# Pressure_SENSOR.net
KiCad netlist of a schematic drawn in Altium Designer
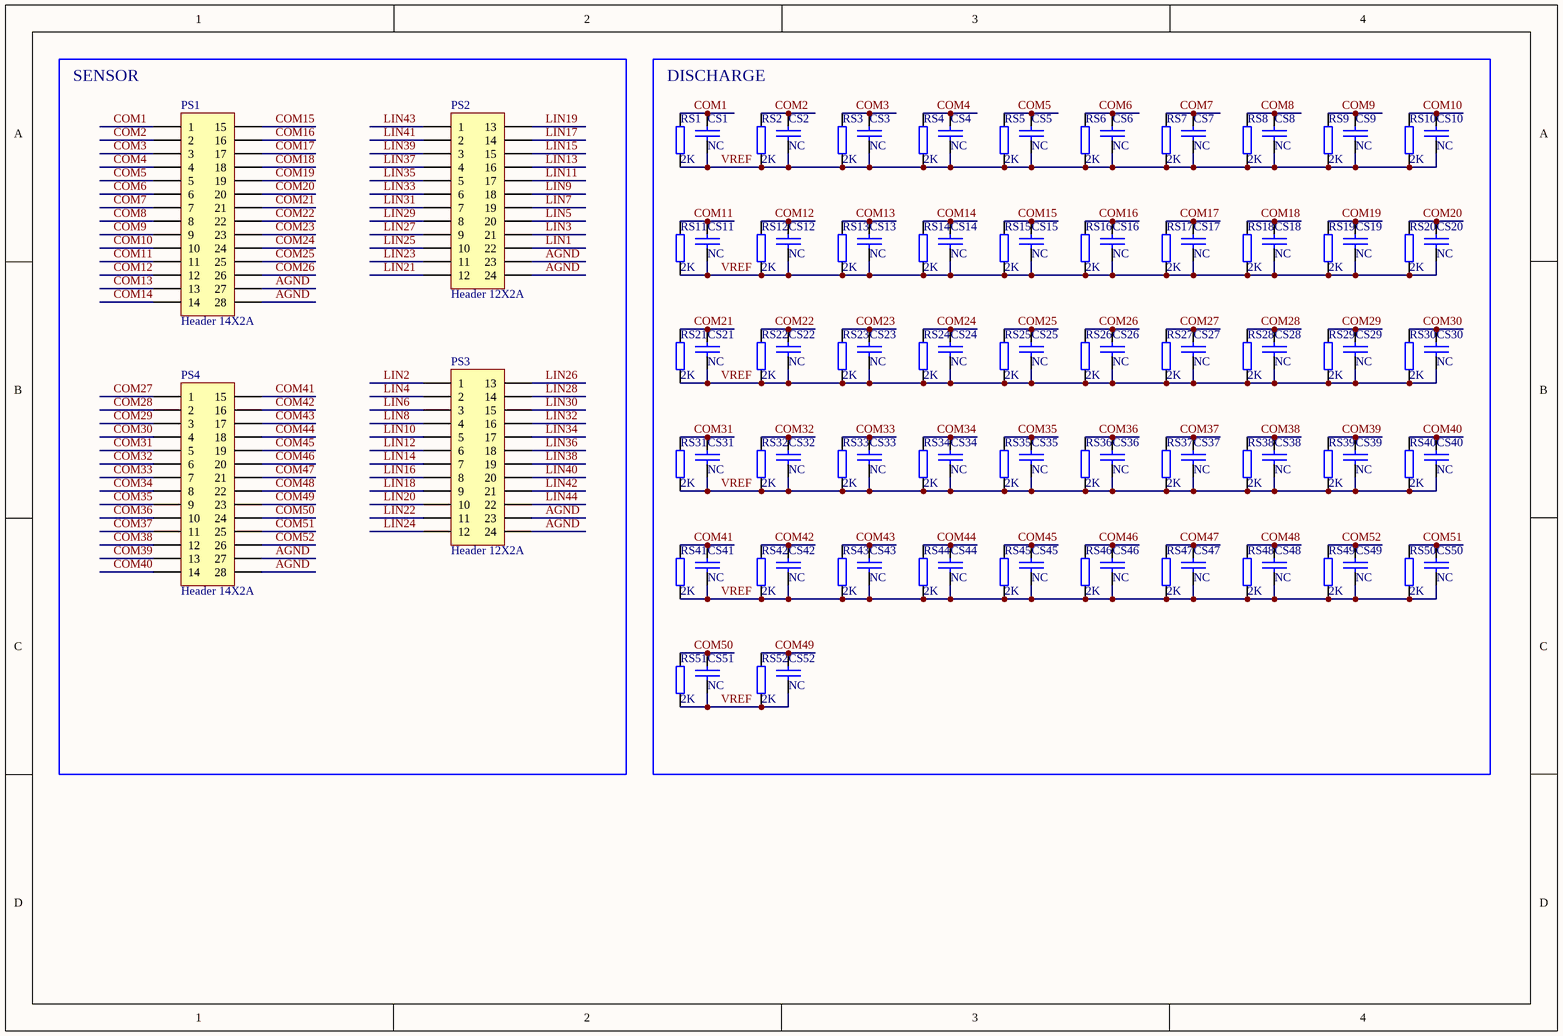
[diagram p0: Pressure_SENSOR.SchDoc]

(export (version "E")
  (design (tool "Eeschema 10.0.6"))
  (components
    (comp (ref "CS1")
      (value "NC")
      (footprint "c0603_HSC100")
      (description "Capacitor")
      (libsource (lib "*") (part "CAP"))
    )
    (comp (ref "CS2")
      (value "NC")
      (footprint "c0603_HSC100")
      (description "Capacitor")
      (libsource (lib "*") (part "CAP"))
    )
    (comp (ref "CS3")
      (value "NC")
      (footprint "c0603_HSC100")
      (description "Capacitor")
      (libsource (lib "*") (part "CAP"))
    )
    (comp (ref "CS4")
      (value "NC")
      (footprint "c0603_HSC100")
      (description "Capacitor")
      (libsource (lib "*") (part "CAP"))
    )
    (comp (ref "CS5")
      (value "NC")
      (footprint "c0603_HSC100")
      (description "Capacitor")
      (libsource (lib "*") (part "CAP"))
    )
    (comp (ref "CS6")
      (value "NC")
      (footprint "c0603_HSC100")
      (description "Capacitor")
      (libsource (lib "*") (part "CAP"))
    )
    (comp (ref "CS7")
      (value "NC")
      (footprint "c0603_HSC100")
      (description "Capacitor")
      (libsource (lib "*") (part "CAP"))
    )
    (comp (ref "CS8")
      (value "NC")
      (footprint "c0603_HSC100")
      (description "Capacitor")
      (libsource (lib "*") (part "CAP"))
    )
    (comp (ref "CS9")
      (value "NC")
      (footprint "c0603_HSC100")
      (description "Capacitor")
      (libsource (lib "*") (part "CAP"))
    )
    (comp (ref "CS10")
      (value "NC")
      (footprint "c0603_HSC100")
      (description "Capacitor")
      (libsource (lib "*") (part "CAP"))
    )
    (comp (ref "CS11")
      (value "NC")
      (footprint "c0603_HSC100")
      (description "Capacitor")
      (libsource (lib "*") (part "CAP"))
    )
    (comp (ref "CS12")
      (value "NC")
      (footprint "c0603_HSC100")
      (description "Capacitor")
      (libsource (lib "*") (part "CAP"))
    )
    (comp (ref "CS13")
      (value "NC")
      (footprint "c0603_HSC100")
      (description "Capacitor")
      (libsource (lib "*") (part "CAP"))
    )
    (comp (ref "CS14")
      (value "NC")
      (footprint "c0603_HSC100")
      (description "Capacitor")
      (libsource (lib "*") (part "CAP"))
    )
    (comp (ref "CS15")
      (value "NC")
      (footprint "c0603_HSC100")
      (description "Capacitor")
      (libsource (lib "*") (part "CAP"))
    )
    (comp (ref "CS16")
      (value "NC")
      (footprint "c0603_HSC100")
      (description "Capacitor")
      (libsource (lib "*") (part "CAP"))
    )
    (comp (ref "CS17")
      (value "NC")
      (footprint "c0603_HSC100")
      (description "Capacitor")
      (libsource (lib "*") (part "CAP"))
    )
    (comp (ref "CS18")
      (value "NC")
      (footprint "c0603_HSC100")
      (description "Capacitor")
      (libsource (lib "*") (part "CAP"))
    )
    (comp (ref "CS19")
      (value "NC")
      (footprint "c0603_HSC100")
      (description "Capacitor")
      (libsource (lib "*") (part "CAP"))
    )
    (comp (ref "CS20")
      (value "NC")
      (footprint "c0603_HSC100")
      (description "Capacitor")
      (libsource (lib "*") (part "CAP"))
    )
    (comp (ref "CS21")
      (value "NC")
      (footprint "c0603_HSC100")
      (description "Capacitor")
      (libsource (lib "*") (part "CAP"))
    )
    (comp (ref "CS22")
      (value "NC")
      (footprint "c0603_HSC100")
      (description "Capacitor")
      (libsource (lib "*") (part "CAP"))
    )
    (comp (ref "CS23")
      (value "NC")
      (footprint "c0603_HSC100")
      (description "Capacitor")
      (libsource (lib "*") (part "CAP"))
    )
    (comp (ref "CS24")
      (value "NC")
      (footprint "c0603_HSC100")
      (description "Capacitor")
      (libsource (lib "*") (part "CAP"))
    )
    (comp (ref "CS25")
      (value "NC")
      (footprint "c0603_HSC100")
      (description "Capacitor")
      (libsource (lib "*") (part "CAP"))
    )
    (comp (ref "CS26")
      (value "NC")
      (footprint "c0603_HSC100")
      (description "Capacitor")
      (libsource (lib "*") (part "CAP"))
    )
    (comp (ref "CS27")
      (value "NC")
      (footprint "c0603_HSC100")
      (description "Capacitor")
      (libsource (lib "*") (part "CAP"))
    )
    (comp (ref "CS28")
      (value "NC")
      (footprint "c0603_HSC100")
      (description "Capacitor")
      (libsource (lib "*") (part "CAP"))
    )
    (comp (ref "CS29")
      (value "NC")
      (footprint "c0603_HSC100")
      (description "Capacitor")
      (libsource (lib "*") (part "CAP"))
    )
    (comp (ref "CS30")
      (value "NC")
      (footprint "c0603_HSC100")
      (description "Capacitor")
      (libsource (lib "*") (part "CAP"))
    )
    (comp (ref "CS31")
      (value "NC")
      (footprint "c0603_HSC100")
      (description "Capacitor")
      (libsource (lib "*") (part "CAP"))
    )
    (comp (ref "CS32")
      (value "NC")
      (footprint "c0603_HSC100")
      (description "Capacitor")
      (libsource (lib "*") (part "CAP"))
    )
    (comp (ref "CS33")
      (value "NC")
      (footprint "c0603_HSC100")
      (description "Capacitor")
      (libsource (lib "*") (part "CAP"))
    )
    (comp (ref "CS34")
      (value "NC")
      (footprint "c0603_HSC100")
      (description "Capacitor")
      (libsource (lib "*") (part "CAP"))
    )
    (comp (ref "CS35")
      (value "NC")
      (footprint "c0603_HSC100")
      (description "Capacitor")
      (libsource (lib "*") (part "CAP"))
    )
    (comp (ref "CS36")
      (value "NC")
      (footprint "c0603_HSC100")
      (description "Capacitor")
      (libsource (lib "*") (part "CAP"))
    )
    (comp (ref "CS37")
      (value "NC")
      (footprint "c0603_HSC100")
      (description "Capacitor")
      (libsource (lib "*") (part "CAP"))
    )
    (comp (ref "CS38")
      (value "NC")
      (footprint "c0603_HSC100")
      (description "Capacitor")
      (libsource (lib "*") (part "CAP"))
    )
    (comp (ref "CS39")
      (value "NC")
      (footprint "c0603_HSC100")
      (description "Capacitor")
      (libsource (lib "*") (part "CAP"))
    )
    (comp (ref "CS40")
      (value "NC")
      (footprint "c0603_HSC100")
      (description "Capacitor")
      (libsource (lib "*") (part "CAP"))
    )
    (comp (ref "CS41")
      (value "NC")
      (footprint "c0603_HSC100")
      (description "Capacitor")
      (libsource (lib "*") (part "CAP"))
    )
    (comp (ref "CS42")
      (value "NC")
      (footprint "c0603_HSC100")
      (description "Capacitor")
      (libsource (lib "*") (part "CAP"))
    )
    (comp (ref "CS43")
      (value "NC")
      (footprint "c0603_HSC100")
      (description "Capacitor")
      (libsource (lib "*") (part "CAP"))
    )
    (comp (ref "CS44")
      (value "NC")
      (footprint "c0603_HSC100")
      (description "Capacitor")
      (libsource (lib "*") (part "CAP"))
    )
    (comp (ref "CS45")
      (value "NC")
      (footprint "c0603_HSC100")
      (description "Capacitor")
      (libsource (lib "*") (part "CAP"))
    )
    (comp (ref "CS46")
      (value "NC")
      (footprint "c0603_HSC100")
      (description "Capacitor")
      (libsource (lib "*") (part "CAP"))
    )
    (comp (ref "CS47")
      (value "NC")
      (footprint "c0603_HSC100")
      (description "Capacitor")
      (libsource (lib "*") (part "CAP"))
    )
    (comp (ref "CS48")
      (value "NC")
      (footprint "c0603_HSC100")
      (description "Capacitor")
      (libsource (lib "*") (part "CAP"))
    )
    (comp (ref "CS49")
      (value "NC")
      (footprint "c0603_HSC100")
      (description "Capacitor")
      (libsource (lib "*") (part "CAP"))
    )
    (comp (ref "CS50")
      (value "NC")
      (footprint "c0603_HSC100")
      (description "Capacitor")
      (libsource (lib "*") (part "CAP"))
    )
    (comp (ref "CS51")
      (value "NC")
      (footprint "c0603_HSC100")
      (description "Capacitor")
      (libsource (lib "*") (part "CAP"))
    )
    (comp (ref "CS52")
      (value "NC")
      (footprint "c0603_HSC100")
      (description "Capacitor")
      (libsource (lib "*") (part "CAP"))
    )
    (comp (ref "PS1")
      (value "Header 14X2A")
      (footprint "FPC-1.0-26")
      (description "Header, 14-Pin, Dual row")
      (fields (field (name "PUBLISHER") "Altium Limited"))
      (libsource (lib "Miscellaneous Connectors") (part "Header 14X2A"))
    )
    (comp (ref "PS2")
      (value "Header 12X2A")
      (footprint "FPC-1.0-22")
      (description "Header, 12-Pin, Dual row")
      (fields (field (name "PUBLISHER") "Altium Limited"))
      (libsource (lib "Miscellaneous Connectors") (part "Header 12X2A"))
    )
    (comp (ref "PS3")
      (value "Header 12X2A")
      (footprint "FPC-1.0-22")
      (description "Header, 12-Pin, Dual row")
      (fields (field (name "PUBLISHER") "Altium Limited"))
      (libsource (lib "Miscellaneous Connectors") (part "Header 12X2A"))
    )
    (comp (ref "PS4")
      (value "Header 14X2A")
      (footprint "FPC-1.0-26")
      (description "Header, 14-Pin, Dual row")
      (fields (field (name "PUBLISHER") "Altium Limited"))
      (libsource (lib "Miscellaneous Connectors") (part "Header 14X2A"))
    )
    (comp (ref "RS1") (value "2K") (footprint "R0603_HSC100") (libsource (lib "MY_SCH") (part "RES")))
    (comp (ref "RS2") (value "2K") (footprint "R0603_HSC100") (libsource (lib "MY_SCH") (part "RES")))
    (comp (ref "RS3") (value "2K") (footprint "R0603_HSC100") (libsource (lib "MY_SCH") (part "RES")))
    (comp (ref "RS4") (value "2K") (footprint "R0603_HSC100") (libsource (lib "MY_SCH") (part "RES")))
    (comp (ref "RS5") (value "2K") (footprint "R0603_HSC100") (libsource (lib "MY_SCH") (part "RES")))
    (comp (ref "RS6") (value "2K") (footprint "R0603_HSC100") (libsource (lib "MY_SCH") (part "RES")))
    (comp (ref "RS7") (value "2K") (footprint "R0603_HSC100") (libsource (lib "MY_SCH") (part "RES")))
    (comp (ref "RS8") (value "2K") (footprint "R0603_HSC100") (libsource (lib "MY_SCH") (part "RES")))
    (comp (ref "RS9") (value "2K") (footprint "R0603_HSC100") (libsource (lib "MY_SCH") (part "RES")))
    (comp (ref "RS10") (value "2K") (footprint "R0603_HSC100") (libsource (lib "MY_SCH") (part "RES")))
    (comp (ref "RS11") (value "2K") (footprint "R0603_HSC100") (libsource (lib "MY_SCH") (part "RES")))
    (comp (ref "RS12") (value "2K") (footprint "R0603_HSC100") (libsource (lib "MY_SCH") (part "RES")))
    (comp (ref "RS13") (value "2K") (footprint "R0603_HSC100") (libsource (lib "MY_SCH") (part "RES")))
    (comp (ref "RS14") (value "2K") (footprint "R0603_HSC100") (libsource (lib "MY_SCH") (part "RES")))
    (comp (ref "RS15") (value "2K") (footprint "R0603_HSC100") (libsource (lib "MY_SCH") (part "RES")))
    (comp (ref "RS16") (value "2K") (footprint "R0603_HSC100") (libsource (lib "MY_SCH") (part "RES")))
    (comp (ref "RS17") (value "2K") (footprint "R0603_HSC100") (libsource (lib "MY_SCH") (part "RES")))
    (comp (ref "RS18") (value "2K") (footprint "R0603_HSC100") (libsource (lib "MY_SCH") (part "RES")))
    (comp (ref "RS19") (value "2K") (footprint "R0603_HSC100") (libsource (lib "MY_SCH") (part "RES")))
    (comp (ref "RS20") (value "2K") (footprint "R0603_HSC100") (libsource (lib "MY_SCH") (part "RES")))
    (comp (ref "RS21") (value "2K") (footprint "R0603_HSC100") (libsource (lib "MY_SCH") (part "RES")))
    (comp (ref "RS22") (value "2K") (footprint "R0603_HSC100") (libsource (lib "MY_SCH") (part "RES")))
    (comp (ref "RS23") (value "2K") (footprint "R0603_HSC100") (libsource (lib "MY_SCH") (part "RES")))
    (comp (ref "RS24") (value "2K") (footprint "R0603_HSC100") (libsource (lib "MY_SCH") (part "RES")))
    (comp (ref "RS25") (value "2K") (footprint "R0603_HSC100") (libsource (lib "MY_SCH") (part "RES")))
    (comp (ref "RS26") (value "2K") (footprint "R0603_HSC100") (libsource (lib "MY_SCH") (part "RES")))
    (comp (ref "RS27") (value "2K") (footprint "R0603_HSC100") (libsource (lib "MY_SCH") (part "RES")))
    (comp (ref "RS28") (value "2K") (footprint "R0603_HSC100") (libsource (lib "MY_SCH") (part "RES")))
    (comp (ref "RS29") (value "2K") (footprint "R0603_HSC100") (libsource (lib "MY_SCH") (part "RES")))
    (comp (ref "RS30") (value "2K") (footprint "R0603_HSC100") (libsource (lib "MY_SCH") (part "RES")))
    (comp (ref "RS31") (value "2K") (footprint "R0603_HSC100") (libsource (lib "MY_SCH") (part "RES")))
    (comp (ref "RS32") (value "2K") (footprint "R0603_HSC100") (libsource (lib "MY_SCH") (part "RES")))
    (comp (ref "RS33") (value "2K") (footprint "R0603_HSC100") (libsource (lib "MY_SCH") (part "RES")))
    (comp (ref "RS34") (value "2K") (footprint "R0603_HSC100") (libsource (lib "MY_SCH") (part "RES")))
    (comp (ref "RS35") (value "2K") (footprint "R0603_HSC100") (libsource (lib "MY_SCH") (part "RES")))
    (comp (ref "RS36") (value "2K") (footprint "R0603_HSC100") (libsource (lib "MY_SCH") (part "RES")))
    (comp (ref "RS37") (value "2K") (footprint "R0603_HSC100") (libsource (lib "MY_SCH") (part "RES")))
    (comp (ref "RS38") (value "2K") (footprint "R0603_HSC100") (libsource (lib "MY_SCH") (part "RES")))
    (comp (ref "RS39") (value "2K") (footprint "R0603_HSC100") (libsource (lib "MY_SCH") (part "RES")))
    (comp (ref "RS40") (value "2K") (footprint "R0603_HSC100") (libsource (lib "MY_SCH") (part "RES")))
    (comp (ref "RS41") (value "2K") (footprint "R0603_HSC100") (libsource (lib "MY_SCH") (part "RES")))
    (comp (ref "RS42") (value "2K") (footprint "R0603_HSC100") (libsource (lib "MY_SCH") (part "RES")))
    (comp (ref "RS43") (value "2K") (footprint "R0603_HSC100") (libsource (lib "MY_SCH") (part "RES")))
    (comp (ref "RS44") (value "2K") (footprint "R0603_HSC100") (libsource (lib "MY_SCH") (part "RES")))
    (comp (ref "RS45") (value "2K") (footprint "R0603_HSC100") (libsource (lib "MY_SCH") (part "RES")))
    (comp (ref "RS46") (value "2K") (footprint "R0603_HSC100") (libsource (lib "MY_SCH") (part "RES")))
    (comp (ref "RS47") (value "2K") (footprint "R0603_HSC100") (libsource (lib "MY_SCH") (part "RES")))
    (comp (ref "RS48") (value "2K") (footprint "R0603_HSC100") (libsource (lib "MY_SCH") (part "RES")))
    (comp (ref "RS49") (value "2K") (footprint "R0603_HSC100") (libsource (lib "MY_SCH") (part "RES")))
    (comp (ref "RS50") (value "2K") (footprint "R0603_HSC100") (libsource (lib "MY_SCH") (part "RES")))
    (comp (ref "RS51") (value "2K") (footprint "R0603_HSC100") (libsource (lib "MY_SCH") (part "RES")))
    (comp (ref "RS52") (value "2K") (footprint "R0603_HSC100") (libsource (lib "MY_SCH") (part "RES")))
  )
  (nets
    (net (code "1") (name "/AGND") (class "Default")
      (node (ref "PS1") (pin "27") (pinfunction "27_27") (pintype "passive"))
      (node (ref "PS1") (pin "28") (pinfunction "28_28") (pintype "passive"))
      (node (ref "PS2") (pin "23") (pinfunction "23_23") (pintype "passive"))
      (node (ref "PS2") (pin "24") (pinfunction "24_24") (pintype "passive"))
      (node (ref "PS3") (pin "23") (pinfunction "23_23") (pintype "passive"))
      (node (ref "PS3") (pin "24") (pinfunction "24_24") (pintype "passive"))
      (node (ref "PS4") (pin "27") (pinfunction "27_27") (pintype "passive"))
      (node (ref "PS4") (pin "28") (pinfunction "28_28") (pintype "passive"))
    )
    (net (code "2") (name "/COM1") (class "Default")
      (node (ref "CS1") (pin "2") (pinfunction "2_2") (pintype "passive"))
      (node (ref "PS1") (pin "1") (pinfunction "1_1") (pintype "passive"))
      (node (ref "RS1") (pin "2") (pintype "passive"))
    )
    (net (code "3") (name "/COM2") (class "Default")
      (node (ref "CS2") (pin "2") (pinfunction "2_2") (pintype "passive"))
      (node (ref "PS1") (pin "2") (pinfunction "2_2") (pintype "passive"))
      (node (ref "RS2") (pin "2") (pintype "passive"))
    )
    (net (code "4") (name "/COM3") (class "Default")
      (node (ref "CS3") (pin "2") (pinfunction "2_2") (pintype "passive"))
      (node (ref "PS1") (pin "3") (pinfunction "3_3") (pintype "passive"))
      (node (ref "RS3") (pin "2") (pintype "passive"))
    )
    (net (code "5") (name "/COM4") (class "Default")
      (node (ref "CS4") (pin "2") (pinfunction "2_2") (pintype "passive"))
      (node (ref "PS1") (pin "4") (pinfunction "4_4") (pintype "passive"))
      (node (ref "RS4") (pin "2") (pintype "passive"))
    )
    (net (code "6") (name "/COM5") (class "Default")
      (node (ref "CS5") (pin "2") (pinfunction "2_2") (pintype "passive"))
      (node (ref "PS1") (pin "5") (pinfunction "5_5") (pintype "passive"))
      (node (ref "RS5") (pin "2") (pintype "passive"))
    )
    (net (code "7") (name "/COM6") (class "Default")
      (node (ref "CS6") (pin "2") (pinfunction "2_2") (pintype "passive"))
      (node (ref "PS1") (pin "6") (pinfunction "6_6") (pintype "passive"))
      (node (ref "RS6") (pin "2") (pintype "passive"))
    )
    (net (code "8") (name "/COM7") (class "Default")
      (node (ref "CS7") (pin "2") (pinfunction "2_2") (pintype "passive"))
      (node (ref "PS1") (pin "7") (pinfunction "7_7") (pintype "passive"))
      (node (ref "RS7") (pin "2") (pintype "passive"))
    )
    (net (code "9") (name "/COM8") (class "Default")
      (node (ref "CS8") (pin "2") (pinfunction "2_2") (pintype "passive"))
      (node (ref "PS1") (pin "8") (pinfunction "8_8") (pintype "passive"))
      (node (ref "RS8") (pin "2") (pintype "passive"))
    )
    (net (code "10") (name "/COM9") (class "Default")
      (node (ref "CS9") (pin "2") (pinfunction "2_2") (pintype "passive"))
      (node (ref "PS1") (pin "9") (pinfunction "9_9") (pintype "passive"))
      (node (ref "RS9") (pin "2") (pintype "passive"))
    )
    (net (code "11") (name "/COM10") (class "Default")
      (node (ref "CS10") (pin "2") (pinfunction "2_2") (pintype "passive"))
      (node (ref "PS1") (pin "10") (pinfunction "10_10") (pintype "passive"))
      (node (ref "RS10") (pin "2") (pintype "passive"))
    )
    (net (code "12") (name "/COM11") (class "Default")
      (node (ref "CS11") (pin "2") (pinfunction "2_2") (pintype "passive"))
      (node (ref "PS1") (pin "11") (pinfunction "11_11") (pintype "passive"))
      (node (ref "RS11") (pin "2") (pintype "passive"))
    )
    (net (code "13") (name "/COM12") (class "Default")
      (node (ref "CS12") (pin "2") (pinfunction "2_2") (pintype "passive"))
      (node (ref "PS1") (pin "12") (pinfunction "12_12") (pintype "passive"))
      (node (ref "RS12") (pin "2") (pintype "passive"))
    )
    (net (code "14") (name "/COM13") (class "Default")
      (node (ref "CS13") (pin "2") (pinfunction "2_2") (pintype "passive"))
      (node (ref "PS1") (pin "13") (pinfunction "13_13") (pintype "passive"))
      (node (ref "RS13") (pin "2") (pintype "passive"))
    )
    (net (code "15") (name "/COM14") (class "Default")
      (node (ref "CS14") (pin "2") (pinfunction "2_2") (pintype "passive"))
      (node (ref "PS1") (pin "14") (pinfunction "14_14") (pintype "passive"))
      (node (ref "RS14") (pin "2") (pintype "passive"))
    )
    (net (code "16") (name "/COM15") (class "Default")
      (node (ref "CS15") (pin "2") (pinfunction "2_2") (pintype "passive"))
      (node (ref "PS1") (pin "15") (pinfunction "15_15") (pintype "passive"))
      (node (ref "RS15") (pin "2") (pintype "passive"))
    )
    (net (code "17") (name "/COM16") (class "Default")
      (node (ref "CS16") (pin "2") (pinfunction "2_2") (pintype "passive"))
      (node (ref "PS1") (pin "16") (pinfunction "16_16") (pintype "passive"))
      (node (ref "RS16") (pin "2") (pintype "passive"))
    )
    (net (code "18") (name "/COM17") (class "Default")
      (node (ref "CS17") (pin "2") (pinfunction "2_2") (pintype "passive"))
      (node (ref "PS1") (pin "17") (pinfunction "17_17") (pintype "passive"))
      (node (ref "RS17") (pin "2") (pintype "passive"))
    )
    (net (code "19") (name "/COM18") (class "Default")
      (node (ref "CS18") (pin "2") (pinfunction "2_2") (pintype "passive"))
      (node (ref "PS1") (pin "18") (pinfunction "18_18") (pintype "passive"))
      (node (ref "RS18") (pin "2") (pintype "passive"))
    )
    (net (code "20") (name "/COM19") (class "Default")
      (node (ref "CS19") (pin "2") (pinfunction "2_2") (pintype "passive"))
      (node (ref "PS1") (pin "19") (pinfunction "19_19") (pintype "passive"))
      (node (ref "RS19") (pin "2") (pintype "passive"))
    )
    (net (code "21") (name "/COM20") (class "Default")
      (node (ref "CS20") (pin "2") (pinfunction "2_2") (pintype "passive"))
      (node (ref "PS1") (pin "20") (pinfunction "20_20") (pintype "passive"))
      (node (ref "RS20") (pin "2") (pintype "passive"))
    )
    (net (code "22") (name "/COM21") (class "Default")
      (node (ref "CS21") (pin "2") (pinfunction "2_2") (pintype "passive"))
      (node (ref "PS1") (pin "21") (pinfunction "21_21") (pintype "passive"))
      (node (ref "RS21") (pin "2") (pintype "passive"))
    )
    (net (code "23") (name "/COM22") (class "Default")
      (node (ref "CS22") (pin "2") (pinfunction "2_2") (pintype "passive"))
      (node (ref "PS1") (pin "22") (pinfunction "22_22") (pintype "passive"))
      (node (ref "RS22") (pin "2") (pintype "passive"))
    )
    (net (code "24") (name "/COM23") (class "Default")
      (node (ref "CS23") (pin "2") (pinfunction "2_2") (pintype "passive"))
      (node (ref "PS1") (pin "23") (pinfunction "23_23") (pintype "passive"))
      (node (ref "RS23") (pin "2") (pintype "passive"))
    )
    (net (code "25") (name "/COM24") (class "Default")
      (node (ref "CS24") (pin "2") (pinfunction "2_2") (pintype "passive"))
      (node (ref "PS1") (pin "24") (pinfunction "24_24") (pintype "passive"))
      (node (ref "RS24") (pin "2") (pintype "passive"))
    )
    (net (code "26") (name "/COM25") (class "Default")
      (node (ref "CS25") (pin "2") (pinfunction "2_2") (pintype "passive"))
      (node (ref "PS1") (pin "25") (pinfunction "25_25") (pintype "passive"))
      (node (ref "RS25") (pin "2") (pintype "passive"))
    )
    (net (code "27") (name "/COM26") (class "Default")
      (node (ref "CS26") (pin "2") (pinfunction "2_2") (pintype "passive"))
      (node (ref "PS1") (pin "26") (pinfunction "26_26") (pintype "passive"))
      (node (ref "RS26") (pin "2") (pintype "passive"))
    )
    (net (code "28") (name "/COM27") (class "Default")
      (node (ref "CS27") (pin "2") (pinfunction "2_2") (pintype "passive"))
      (node (ref "PS4") (pin "1") (pinfunction "1_1") (pintype "passive"))
      (node (ref "RS27") (pin "2") (pintype "passive"))
    )
    (net (code "29") (name "/COM28") (class "Default")
      (node (ref "CS28") (pin "2") (pinfunction "2_2") (pintype "passive"))
      (node (ref "PS4") (pin "2") (pinfunction "2_2") (pintype "passive"))
      (node (ref "RS28") (pin "2") (pintype "passive"))
    )
    (net (code "30") (name "/COM29") (class "Default")
      (node (ref "CS29") (pin "2") (pinfunction "2_2") (pintype "passive"))
      (node (ref "PS4") (pin "3") (pinfunction "3_3") (pintype "passive"))
      (node (ref "RS29") (pin "2") (pintype "passive"))
    )
    (net (code "31") (name "/COM30") (class "Default")
      (node (ref "CS30") (pin "2") (pinfunction "2_2") (pintype "passive"))
      (node (ref "PS4") (pin "4") (pinfunction "4_4") (pintype "passive"))
      (node (ref "RS30") (pin "2") (pintype "passive"))
    )
    (net (code "32") (name "/COM31") (class "Default")
      (node (ref "CS31") (pin "2") (pinfunction "2_2") (pintype "passive"))
      (node (ref "PS4") (pin "5") (pinfunction "5_5") (pintype "passive"))
      (node (ref "RS31") (pin "2") (pintype "passive"))
    )
    (net (code "33") (name "/COM32") (class "Default")
      (node (ref "CS32") (pin "2") (pinfunction "2_2") (pintype "passive"))
      (node (ref "PS4") (pin "6") (pinfunction "6_6") (pintype "passive"))
      (node (ref "RS32") (pin "2") (pintype "passive"))
    )
    (net (code "34") (name "/COM33") (class "Default")
      (node (ref "CS33") (pin "2") (pinfunction "2_2") (pintype "passive"))
      (node (ref "PS4") (pin "7") (pinfunction "7_7") (pintype "passive"))
      (node (ref "RS33") (pin "2") (pintype "passive"))
    )
    (net (code "35") (name "/COM34") (class "Default")
      (node (ref "CS34") (pin "2") (pinfunction "2_2") (pintype "passive"))
      (node (ref "PS4") (pin "8") (pinfunction "8_8") (pintype "passive"))
      (node (ref "RS34") (pin "2") (pintype "passive"))
    )
    (net (code "36") (name "/COM35") (class "Default")
      (node (ref "CS35") (pin "2") (pinfunction "2_2") (pintype "passive"))
      (node (ref "PS4") (pin "9") (pinfunction "9_9") (pintype "passive"))
      (node (ref "RS35") (pin "2") (pintype "passive"))
    )
    (net (code "37") (name "/COM36") (class "Default")
      (node (ref "CS36") (pin "2") (pinfunction "2_2") (pintype "passive"))
      (node (ref "PS4") (pin "10") (pinfunction "10_10") (pintype "passive"))
      (node (ref "RS36") (pin "2") (pintype "passive"))
    )
    (net (code "38") (name "/COM37") (class "Default")
      (node (ref "CS37") (pin "2") (pinfunction "2_2") (pintype "passive"))
      (node (ref "PS4") (pin "11") (pinfunction "11_11") (pintype "passive"))
      (node (ref "RS37") (pin "2") (pintype "passive"))
    )
    (net (code "39") (name "/COM38") (class "Default")
      (node (ref "CS38") (pin "2") (pinfunction "2_2") (pintype "passive"))
      (node (ref "PS4") (pin "12") (pinfunction "12_12") (pintype "passive"))
      (node (ref "RS38") (pin "2") (pintype "passive"))
    )
    (net (code "40") (name "/COM39") (class "Default")
      (node (ref "CS39") (pin "2") (pinfunction "2_2") (pintype "passive"))
      (node (ref "PS4") (pin "13") (pinfunction "13_13") (pintype "passive"))
      (node (ref "RS39") (pin "2") (pintype "passive"))
    )
    (net (code "41") (name "/COM40") (class "Default")
      (node (ref "CS40") (pin "2") (pinfunction "2_2") (pintype "passive"))
      (node (ref "PS4") (pin "14") (pinfunction "14_14") (pintype "passive"))
      (node (ref "RS40") (pin "2") (pintype "passive"))
    )
    (net (code "42") (name "/COM41") (class "Default")
      (node (ref "CS41") (pin "2") (pinfunction "2_2") (pintype "passive"))
      (node (ref "PS4") (pin "15") (pinfunction "15_15") (pintype "passive"))
      (node (ref "RS41") (pin "2") (pintype "passive"))
    )
    (net (code "43") (name "/COM42") (class "Default")
      (node (ref "CS42") (pin "2") (pinfunction "2_2") (pintype "passive"))
      (node (ref "PS4") (pin "16") (pinfunction "16_16") (pintype "passive"))
      (node (ref "RS42") (pin "2") (pintype "passive"))
    )
    (net (code "44") (name "/COM43") (class "Default")
      (node (ref "CS43") (pin "2") (pinfunction "2_2") (pintype "passive"))
      (node (ref "PS4") (pin "17") (pinfunction "17_17") (pintype "passive"))
      (node (ref "RS43") (pin "2") (pintype "passive"))
    )
    (net (code "45") (name "/COM44") (class "Default")
      (node (ref "CS44") (pin "2") (pinfunction "2_2") (pintype "passive"))
      (node (ref "PS4") (pin "18") (pinfunction "18_18") (pintype "passive"))
      (node (ref "RS44") (pin "2") (pintype "passive"))
    )
    (net (code "46") (name "/COM45") (class "Default")
      (node (ref "CS45") (pin "2") (pinfunction "2_2") (pintype "passive"))
      (node (ref "PS4") (pin "19") (pinfunction "19_19") (pintype "passive"))
      (node (ref "RS45") (pin "2") (pintype "passive"))
    )
    (net (code "47") (name "/COM46") (class "Default")
      (node (ref "CS46") (pin "2") (pinfunction "2_2") (pintype "passive"))
      (node (ref "PS4") (pin "20") (pinfunction "20_20") (pintype "passive"))
      (node (ref "RS46") (pin "2") (pintype "passive"))
    )
    (net (code "48") (name "/COM47") (class "Default")
      (node (ref "CS47") (pin "2") (pinfunction "2_2") (pintype "passive"))
      (node (ref "PS4") (pin "21") (pinfunction "21_21") (pintype "passive"))
      (node (ref "RS47") (pin "2") (pintype "passive"))
    )
    (net (code "49") (name "/COM48") (class "Default")
      (node (ref "CS48") (pin "2") (pinfunction "2_2") (pintype "passive"))
      (node (ref "PS4") (pin "22") (pinfunction "22_22") (pintype "passive"))
      (node (ref "RS48") (pin "2") (pintype "passive"))
    )
    (net (code "50") (name "/COM49") (class "Default")
      (node (ref "CS52") (pin "2") (pinfunction "2_2") (pintype "passive"))
      (node (ref "PS4") (pin "23") (pinfunction "23_23") (pintype "passive"))
      (node (ref "RS52") (pin "2") (pintype "passive"))
    )
    (net (code "51") (name "/COM50") (class "Default")
      (node (ref "CS51") (pin "2") (pinfunction "2_2") (pintype "passive"))
      (node (ref "PS4") (pin "24") (pinfunction "24_24") (pintype "passive"))
      (node (ref "RS51") (pin "2") (pintype "passive"))
    )
    (net (code "52") (name "/COM51") (class "Default")
      (node (ref "CS50") (pin "2") (pinfunction "2_2") (pintype "passive"))
      (node (ref "PS4") (pin "25") (pinfunction "25_25") (pintype "passive"))
      (node (ref "RS50") (pin "2") (pintype "passive"))
    )
    (net (code "53") (name "/COM52") (class "Default")
      (node (ref "CS49") (pin "2") (pinfunction "2_2") (pintype "passive"))
      (node (ref "PS4") (pin "26") (pinfunction "26_26") (pintype "passive"))
      (node (ref "RS49") (pin "2") (pintype "passive"))
    )
    (net (code "54") (name "/LIN1") (class "Default")
      (node (ref "PS2") (pin "22") (pinfunction "22_22") (pintype "passive"))
    )
    (net (code "55") (name "/LIN2") (class "Default")
      (node (ref "PS3") (pin "1") (pinfunction "1_1") (pintype "passive"))
    )
    (net (code "56") (name "/LIN3") (class "Default")
      (node (ref "PS2") (pin "21") (pinfunction "21_21") (pintype "passive"))
    )
    (net (code "57") (name "/LIN4") (class "Default")
      (node (ref "PS3") (pin "2") (pinfunction "2_2") (pintype "passive"))
    )
    (net (code "58") (name "/LIN5") (class "Default")
      (node (ref "PS2") (pin "20") (pinfunction "20_20") (pintype "passive"))
    )
    (net (code "59") (name "/LIN6") (class "Default")
      (node (ref "PS3") (pin "3") (pinfunction "3_3") (pintype "passive"))
    )
    (net (code "60") (name "/LIN7") (class "Default")
      (node (ref "PS2") (pin "19") (pinfunction "19_19") (pintype "passive"))
    )
    (net (code "61") (name "/LIN8") (class "Default")
      (node (ref "PS3") (pin "4") (pinfunction "4_4") (pintype "passive"))
    )
    (net (code "62") (name "/LIN9") (class "Default")
      (node (ref "PS2") (pin "18") (pinfunction "18_18") (pintype "passive"))
    )
    (net (code "63") (name "/LIN10") (class "Default")
      (node (ref "PS3") (pin "5") (pinfunction "5_5") (pintype "passive"))
    )
    (net (code "64") (name "/LIN11") (class "Default")
      (node (ref "PS2") (pin "17") (pinfunction "17_17") (pintype "passive"))
    )
    (net (code "65") (name "/LIN12") (class "Default")
      (node (ref "PS3") (pin "6") (pinfunction "6_6") (pintype "passive"))
    )
    (net (code "66") (name "/LIN13") (class "Default")
      (node (ref "PS2") (pin "16") (pinfunction "16_16") (pintype "passive"))
    )
    (net (code "67") (name "/LIN14") (class "Default")
      (node (ref "PS3") (pin "7") (pinfunction "7_7") (pintype "passive"))
    )
    (net (code "68") (name "/LIN15") (class "Default")
      (node (ref "PS2") (pin "15") (pinfunction "15_15") (pintype "passive"))
    )
    (net (code "69") (name "/LIN16") (class "Default")
      (node (ref "PS3") (pin "8") (pinfunction "8_8") (pintype "passive"))
    )
    (net (code "70") (name "/LIN17") (class "Default")
      (node (ref "PS2") (pin "14") (pinfunction "14_14") (pintype "passive"))
    )
    (net (code "71") (name "/LIN18") (class "Default")
      (node (ref "PS3") (pin "9") (pinfunction "9_9") (pintype "passive"))
    )
    (net (code "72") (name "/LIN19") (class "Default")
      (node (ref "PS2") (pin "13") (pinfunction "13_13") (pintype "passive"))
    )
    (net (code "73") (name "/LIN20") (class "Default")
      (node (ref "PS3") (pin "10") (pinfunction "10_10") (pintype "passive"))
    )
    (net (code "74") (name "/LIN21") (class "Default")
      (node (ref "PS2") (pin "12") (pinfunction "12_12") (pintype "passive"))
    )
    (net (code "75") (name "/LIN22") (class "Default")
      (node (ref "PS3") (pin "11") (pinfunction "11_11") (pintype "passive"))
    )
    (net (code "76") (name "/LIN23") (class "Default")
      (node (ref "PS2") (pin "11") (pinfunction "11_11") (pintype "passive"))
    )
    (net (code "77") (name "/LIN24") (class "Default")
      (node (ref "PS3") (pin "12") (pinfunction "12_12") (pintype "passive"))
    )
    (net (code "78") (name "/LIN25") (class "Default")
      (node (ref "PS2") (pin "10") (pinfunction "10_10") (pintype "passive"))
    )
    (net (code "79") (name "/LIN26") (class "Default")
      (node (ref "PS3") (pin "13") (pinfunction "13_13") (pintype "passive"))
    )
    (net (code "80") (name "/LIN27") (class "Default")
      (node (ref "PS2") (pin "9") (pinfunction "9_9") (pintype "passive"))
    )
    (net (code "81") (name "/LIN28") (class "Default")
      (node (ref "PS3") (pin "14") (pinfunction "14_14") (pintype "passive"))
    )
    (net (code "82") (name "/LIN29") (class "Default")
      (node (ref "PS2") (pin "8") (pinfunction "8_8") (pintype "passive"))
    )
    (net (code "83") (name "/LIN30") (class "Default")
      (node (ref "PS3") (pin "15") (pinfunction "15_15") (pintype "passive"))
    )
    (net (code "84") (name "/LIN31") (class "Default")
      (node (ref "PS2") (pin "7") (pinfunction "7_7") (pintype "passive"))
    )
    (net (code "85") (name "/LIN32") (class "Default")
      (node (ref "PS3") (pin "16") (pinfunction "16_16") (pintype "passive"))
    )
    (net (code "86") (name "/LIN33") (class "Default")
      (node (ref "PS2") (pin "6") (pinfunction "6_6") (pintype "passive"))
    )
    (net (code "87") (name "/LIN34") (class "Default")
      (node (ref "PS3") (pin "17") (pinfunction "17_17") (pintype "passive"))
    )
    (net (code "88") (name "/LIN35") (class "Default")
      (node (ref "PS2") (pin "5") (pinfunction "5_5") (pintype "passive"))
    )
    (net (code "89") (name "/LIN36") (class "Default")
      (node (ref "PS3") (pin "18") (pinfunction "18_18") (pintype "passive"))
    )
    (net (code "90") (name "/LIN37") (class "Default")
      (node (ref "PS2") (pin "4") (pinfunction "4_4") (pintype "passive"))
    )
    (net (code "91") (name "/LIN38") (class "Default")
      (node (ref "PS3") (pin "19") (pinfunction "19_19") (pintype "passive"))
    )
    (net (code "92") (name "/LIN39") (class "Default")
      (node (ref "PS2") (pin "3") (pinfunction "3_3") (pintype "passive"))
    )
    (net (code "93") (name "/LIN40") (class "Default")
      (node (ref "PS3") (pin "20") (pinfunction "20_20") (pintype "passive"))
    )
    (net (code "94") (name "/LIN41") (class "Default")
      (node (ref "PS2") (pin "2") (pinfunction "2_2") (pintype "passive"))
    )
    (net (code "95") (name "/LIN42") (class "Default")
      (node (ref "PS3") (pin "21") (pinfunction "21_21") (pintype "passive"))
    )
    (net (code "96") (name "/LIN43") (class "Default")
      (node (ref "PS2") (pin "1") (pinfunction "1_1") (pintype "passive"))
    )
    (net (code "97") (name "/LIN44") (class "Default")
      (node (ref "PS3") (pin "22") (pinfunction "22_22") (pintype "passive"))
    )
    (net (code "98") (name "/VREF") (class "Default")
      (node (ref "CS1") (pin "1") (pinfunction "1_1") (pintype "passive"))
      (node (ref "CS10") (pin "1") (pinfunction "1_1") (pintype "passive"))
      (node (ref "CS11") (pin "1") (pinfunction "1_1") (pintype "passive"))
      (node (ref "CS12") (pin "1") (pinfunction "1_1") (pintype "passive"))
      (node (ref "CS13") (pin "1") (pinfunction "1_1") (pintype "passive"))
      (node (ref "CS14") (pin "1") (pinfunction "1_1") (pintype "passive"))
      (node (ref "CS15") (pin "1") (pinfunction "1_1") (pintype "passive"))
      (node (ref "CS16") (pin "1") (pinfunction "1_1") (pintype "passive"))
      (node (ref "CS17") (pin "1") (pinfunction "1_1") (pintype "passive"))
      (node (ref "CS18") (pin "1") (pinfunction "1_1") (pintype "passive"))
      (node (ref "CS19") (pin "1") (pinfunction "1_1") (pintype "passive"))
      (node (ref "CS2") (pin "1") (pinfunction "1_1") (pintype "passive"))
      (node (ref "CS20") (pin "1") (pinfunction "1_1") (pintype "passive"))
      (node (ref "CS21") (pin "1") (pinfunction "1_1") (pintype "passive"))
      (node (ref "CS22") (pin "1") (pinfunction "1_1") (pintype "passive"))
      (node (ref "CS23") (pin "1") (pinfunction "1_1") (pintype "passive"))
      (node (ref "CS24") (pin "1") (pinfunction "1_1") (pintype "passive"))
      (node (ref "CS25") (pin "1") (pinfunction "1_1") (pintype "passive"))
      (node (ref "CS26") (pin "1") (pinfunction "1_1") (pintype "passive"))
      (node (ref "CS27") (pin "1") (pinfunction "1_1") (pintype "passive"))
      (node (ref "CS28") (pin "1") (pinfunction "1_1") (pintype "passive"))
      (node (ref "CS29") (pin "1") (pinfunction "1_1") (pintype "passive"))
      (node (ref "CS3") (pin "1") (pinfunction "1_1") (pintype "passive"))
      (node (ref "CS30") (pin "1") (pinfunction "1_1") (pintype "passive"))
      (node (ref "CS31") (pin "1") (pinfunction "1_1") (pintype "passive"))
      (node (ref "CS32") (pin "1") (pinfunction "1_1") (pintype "passive"))
      (node (ref "CS33") (pin "1") (pinfunction "1_1") (pintype "passive"))
      (node (ref "CS34") (pin "1") (pinfunction "1_1") (pintype "passive"))
      (node (ref "CS35") (pin "1") (pinfunction "1_1") (pintype "passive"))
      (node (ref "CS36") (pin "1") (pinfunction "1_1") (pintype "passive"))
      (node (ref "CS37") (pin "1") (pinfunction "1_1") (pintype "passive"))
      (node (ref "CS38") (pin "1") (pinfunction "1_1") (pintype "passive"))
      (node (ref "CS39") (pin "1") (pinfunction "1_1") (pintype "passive"))
      (node (ref "CS4") (pin "1") (pinfunction "1_1") (pintype "passive"))
      (node (ref "CS40") (pin "1") (pinfunction "1_1") (pintype "passive"))
      (node (ref "CS41") (pin "1") (pinfunction "1_1") (pintype "passive"))
      (node (ref "CS42") (pin "1") (pinfunction "1_1") (pintype "passive"))
      (node (ref "CS43") (pin "1") (pinfunction "1_1") (pintype "passive"))
      (node (ref "CS44") (pin "1") (pinfunction "1_1") (pintype "passive"))
      (node (ref "CS45") (pin "1") (pinfunction "1_1") (pintype "passive"))
      (node (ref "CS46") (pin "1") (pinfunction "1_1") (pintype "passive"))
      (node (ref "CS47") (pin "1") (pinfunction "1_1") (pintype "passive"))
      (node (ref "CS48") (pin "1") (pinfunction "1_1") (pintype "passive"))
      (node (ref "CS49") (pin "1") (pinfunction "1_1") (pintype "passive"))
      (node (ref "CS5") (pin "1") (pinfunction "1_1") (pintype "passive"))
      (node (ref "CS50") (pin "1") (pinfunction "1_1") (pintype "passive"))
      (node (ref "CS51") (pin "1") (pinfunction "1_1") (pintype "passive"))
      (node (ref "CS52") (pin "1") (pinfunction "1_1") (pintype "passive"))
      (node (ref "CS6") (pin "1") (pinfunction "1_1") (pintype "passive"))
      (node (ref "CS7") (pin "1") (pinfunction "1_1") (pintype "passive"))
      (node (ref "CS8") (pin "1") (pinfunction "1_1") (pintype "passive"))
      (node (ref "CS9") (pin "1") (pinfunction "1_1") (pintype "passive"))
      (node (ref "RS1") (pin "1") (pintype "passive"))
      (node (ref "RS10") (pin "1") (pintype "passive"))
      (node (ref "RS11") (pin "1") (pintype "passive"))
      (node (ref "RS12") (pin "1") (pintype "passive"))
      (node (ref "RS13") (pin "1") (pintype "passive"))
      (node (ref "RS14") (pin "1") (pintype "passive"))
      (node (ref "RS15") (pin "1") (pintype "passive"))
      (node (ref "RS16") (pin "1") (pintype "passive"))
      (node (ref "RS17") (pin "1") (pintype "passive"))
      (node (ref "RS18") (pin "1") (pintype "passive"))
      (node (ref "RS19") (pin "1") (pintype "passive"))
      (node (ref "RS2") (pin "1") (pintype "passive"))
      (node (ref "RS20") (pin "1") (pintype "passive"))
      (node (ref "RS21") (pin "1") (pintype "passive"))
      (node (ref "RS22") (pin "1") (pintype "passive"))
      (node (ref "RS23") (pin "1") (pintype "passive"))
      (node (ref "RS24") (pin "1") (pintype "passive"))
      (node (ref "RS25") (pin "1") (pintype "passive"))
      (node (ref "RS26") (pin "1") (pintype "passive"))
      (node (ref "RS27") (pin "1") (pintype "passive"))
      (node (ref "RS28") (pin "1") (pintype "passive"))
      (node (ref "RS29") (pin "1") (pintype "passive"))
      (node (ref "RS3") (pin "1") (pintype "passive"))
      (node (ref "RS30") (pin "1") (pintype "passive"))
      (node (ref "RS31") (pin "1") (pintype "passive"))
      (node (ref "RS32") (pin "1") (pintype "passive"))
      (node (ref "RS33") (pin "1") (pintype "passive"))
      (node (ref "RS34") (pin "1") (pintype "passive"))
      (node (ref "RS35") (pin "1") (pintype "passive"))
      (node (ref "RS36") (pin "1") (pintype "passive"))
      (node (ref "RS37") (pin "1") (pintype "passive"))
      (node (ref "RS38") (pin "1") (pintype "passive"))
      (node (ref "RS39") (pin "1") (pintype "passive"))
      (node (ref "RS4") (pin "1") (pintype "passive"))
      (node (ref "RS40") (pin "1") (pintype "passive"))
      (node (ref "RS41") (pin "1") (pintype "passive"))
      (node (ref "RS42") (pin "1") (pintype "passive"))
      (node (ref "RS43") (pin "1") (pintype "passive"))
      (node (ref "RS44") (pin "1") (pintype "passive"))
      (node (ref "RS45") (pin "1") (pintype "passive"))
      (node (ref "RS46") (pin "1") (pintype "passive"))
      (node (ref "RS47") (pin "1") (pintype "passive"))
      (node (ref "RS48") (pin "1") (pintype "passive"))
      (node (ref "RS49") (pin "1") (pintype "passive"))
      (node (ref "RS5") (pin "1") (pintype "passive"))
      (node (ref "RS50") (pin "1") (pintype "passive"))
      (node (ref "RS51") (pin "1") (pintype "passive"))
      (node (ref "RS52") (pin "1") (pintype "passive"))
      (node (ref "RS6") (pin "1") (pintype "passive"))
      (node (ref "RS7") (pin "1") (pintype "passive"))
      (node (ref "RS8") (pin "1") (pintype "passive"))
      (node (ref "RS9") (pin "1") (pintype "passive"))
    )
  )
)
